# mctl5.net
KiCad netlist of a schematic drawn in EAGLE
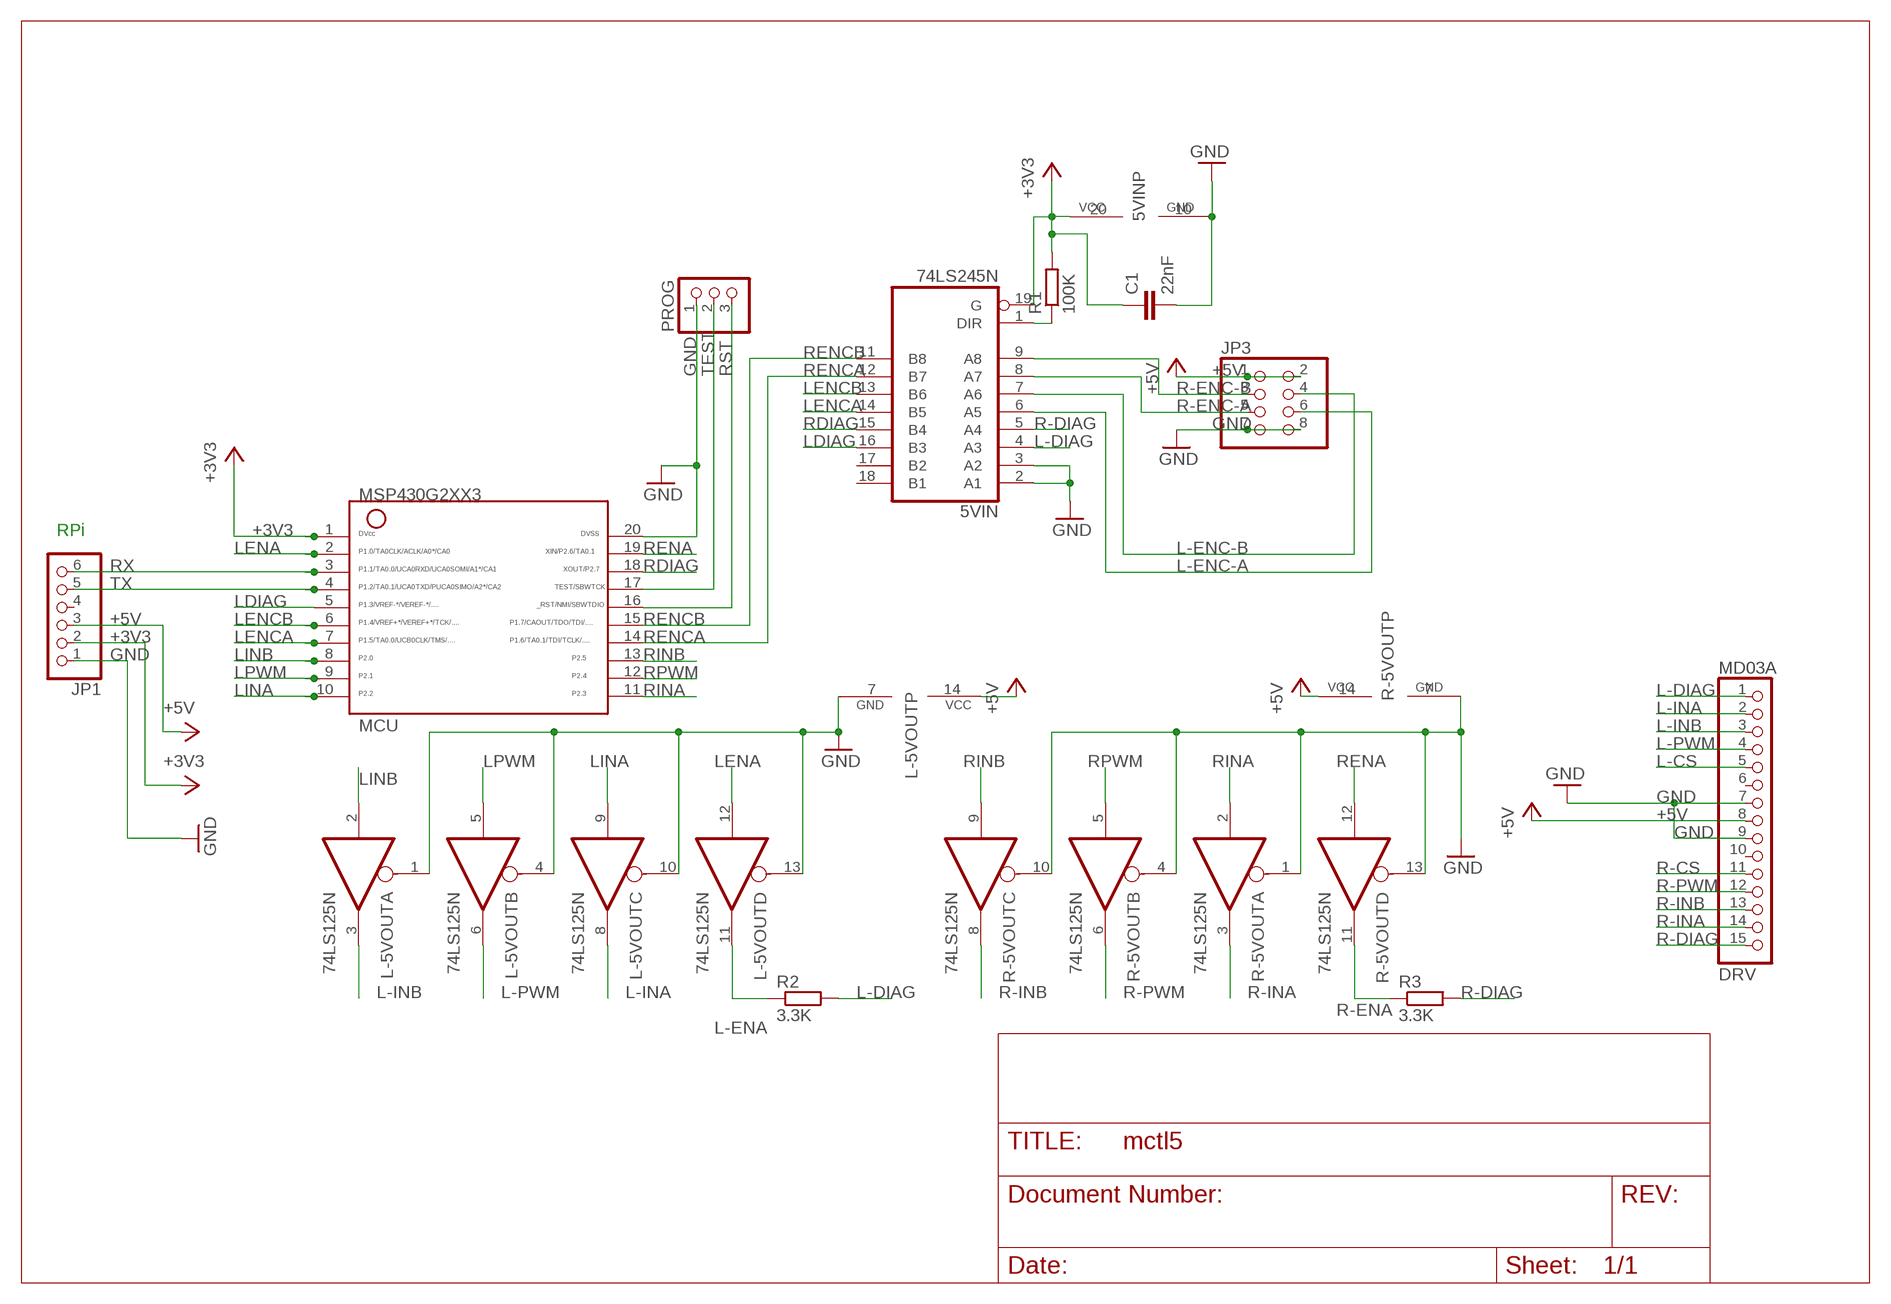
[diagram p0: schematic, sheet 1]

(export (version "E")
  (design (tool "Eeschema 10.0.6"))
  (components
    (comp (ref "5VIN")
      (value "74LS245N")
      (footprint "eagle-import:DIL20")
      (libsource (lib "eagle-import") (part "74245NLS"))
    )
    (comp (ref "C1")
      (value "22nF")
      (footprint "eagle-import:C025-024X044")
      (libsource (lib "eagle-import") (part "C-EU025-024X044"))
    )
    (comp (ref "JP1")
      (value "PINHD-1X6")
      (footprint "eagle-import:1X06")
      (libsource (lib "eagle-import") (part "PINHD-1X6"))
    )
    (comp (ref "JP3")
      (value "PINHD-2X4")
      (footprint "eagle-import:2X04")
      (libsource (lib "eagle-import") (part "PINHD-2X4"))
    )
    (comp (ref "L-5VOUT")
      (value "74LS125N")
      (footprint "eagle-import:DIL14")
      (libsource (lib "eagle-import") (part "74125NLS"))
    )
    (comp (ref "MCU")
      (value "G2XX3---N20")
      (footprint "eagle-import:N20")
      (libsource (lib "eagle-import") (part "G2XX3---N20"))
    )
    (comp (ref "MD03A")
      (value "DRV")
      (footprint "eagle-import:1X15-CB")
      (libsource (lib "eagle-import") (part "PINHD-1X15-CB"))
    )
    (comp (ref "PROG")
      (value "PINHD-1X3")
      (footprint "eagle-import:1X03")
      (libsource (lib "eagle-import") (part "PINHD-1X3"))
    )
    (comp (ref "R-5VOUT")
      (value "74LS125N")
      (footprint "eagle-import:DIL14")
      (libsource (lib "eagle-import") (part "74125NLS"))
    )
    (comp (ref "R1")
      (value "100K")
      (footprint "eagle-import:0204_7")
      (libsource (lib "eagle-import") (part "R-EU_0204/7"))
    )
    (comp (ref "R2")
      (value "3.3K")
      (footprint "eagle-import:0204_7")
      (libsource (lib "eagle-import") (part "R-EU_0204/7"))
    )
    (comp (ref "R3")
      (value "3.3K")
      (footprint "eagle-import:0204_7")
      (libsource (lib "eagle-import") (part "R-EU_0204/7"))
    )
  )
  (nets
    (net (code "1") (name "+3V3") (class "Default")
      (node (ref "5VIN") (pin "19") (pinfunction "G_19") (pintype "input"))
      (node (ref "5VIN") (pin "20") (pinfunction "VCC_20") (pintype "power_in"))
      (node (ref "C1") (pin "1") (pinfunction "1_1") (pintype "passive"))
      (node (ref "JP1") (pin "2") (pinfunction "2_2") (pintype "passive"))
      (node (ref "MCU") (pin "1") (pinfunction "1_1") (pintype "bidirectional"))
      (node (ref "R1") (pin "2") (pinfunction "2_2") (pintype "passive"))
    )
    (net (code "2") (name "+5V") (class "Default")
      (node (ref "JP1") (pin "3") (pinfunction "3_3") (pintype "passive"))
      (node (ref "JP3") (pin "1") (pinfunction "1_1") (pintype "passive"))
      (node (ref "JP3") (pin "2") (pinfunction "2_2") (pintype "passive"))
      (node (ref "L-5VOUT") (pin "14") (pinfunction "VCC_14") (pintype "power_in"))
      (node (ref "MD03A") (pin "8") (pinfunction "8_8") (pintype "passive"))
      (node (ref "R-5VOUT") (pin "14") (pinfunction "VCC_14") (pintype "power_in"))
    )
    (net (code "3") (name "/L-CS") (class "Default")
      (node (ref "MD03A") (pin "5") (pinfunction "5_5") (pintype "passive"))
    )
    (net (code "4") (name "/L-DIAG") (class "Default")
      (node (ref "5VIN") (pin "4") (pinfunction "A3_4") (pintype "bidirectional"))
      (node (ref "MD03A") (pin "1") (pinfunction "1_1") (pintype "passive"))
      (node (ref "R2") (pin "2") (pinfunction "2_2") (pintype "passive"))
    )
    (net (code "5") (name "/L-ENA") (class "Default")
      (node (ref "L-5VOUT") (pin "11") (pinfunction "O_11") (pintype "tri_state"))
      (node (ref "R2") (pin "1") (pinfunction "1_1") (pintype "passive"))
    )
    (net (code "6") (name "/L-ENC-A") (class "Default")
      (node (ref "5VIN") (pin "6") (pinfunction "A5_6") (pintype "bidirectional"))
      (node (ref "JP3") (pin "6") (pinfunction "6_6") (pintype "passive"))
    )
    (net (code "7") (name "/L-ENC-B") (class "Default")
      (node (ref "5VIN") (pin "7") (pinfunction "A6_7") (pintype "bidirectional"))
      (node (ref "JP3") (pin "4") (pinfunction "4_4") (pintype "passive"))
    )
    (net (code "8") (name "/L-INA") (class "Default")
      (node (ref "L-5VOUT") (pin "8") (pinfunction "O_8") (pintype "tri_state"))
      (node (ref "MD03A") (pin "2") (pinfunction "2_2") (pintype "passive"))
    )
    (net (code "9") (name "/L-INB") (class "Default")
      (node (ref "L-5VOUT") (pin "3") (pinfunction "O_3") (pintype "tri_state"))
      (node (ref "MD03A") (pin "3") (pinfunction "3_3") (pintype "passive"))
    )
    (net (code "10") (name "/L-PWM") (class "Default")
      (node (ref "L-5VOUT") (pin "6") (pinfunction "O_6") (pintype "tri_state"))
      (node (ref "MD03A") (pin "4") (pinfunction "4_4") (pintype "passive"))
    )
    (net (code "11") (name "/LDIAG") (class "Default")
      (node (ref "5VIN") (pin "16") (pinfunction "B3_16") (pintype "bidirectional"))
      (node (ref "MCU") (pin "5") (pinfunction "5_5") (pintype "bidirectional"))
    )
    (net (code "12") (name "/LENA") (class "Default")
      (node (ref "L-5VOUT") (pin "12") (pinfunction "I_12") (pintype "input"))
      (node (ref "MCU") (pin "2") (pinfunction "2_2") (pintype "bidirectional"))
    )
    (net (code "13") (name "/LENCA") (class "Default")
      (node (ref "5VIN") (pin "14") (pinfunction "B5_14") (pintype "bidirectional"))
      (node (ref "MCU") (pin "7") (pinfunction "7_7") (pintype "bidirectional"))
    )
    (net (code "14") (name "/LENCB") (class "Default")
      (node (ref "5VIN") (pin "13") (pinfunction "B6_13") (pintype "bidirectional"))
      (node (ref "MCU") (pin "6") (pinfunction "6_6") (pintype "bidirectional"))
    )
    (net (code "15") (name "/LINA") (class "Default")
      (node (ref "L-5VOUT") (pin "9") (pinfunction "I_9") (pintype "input"))
      (node (ref "MCU") (pin "10") (pinfunction "10_10") (pintype "bidirectional"))
    )
    (net (code "16") (name "/LINB") (class "Default")
      (node (ref "L-5VOUT") (pin "2") (pinfunction "I_2") (pintype "input"))
      (node (ref "MCU") (pin "8") (pinfunction "8_8") (pintype "bidirectional"))
    )
    (net (code "17") (name "/LPWM") (class "Default")
      (node (ref "L-5VOUT") (pin "5") (pinfunction "I_5") (pintype "input"))
      (node (ref "MCU") (pin "9") (pinfunction "9_9") (pintype "bidirectional"))
    )
    (net (code "18") (name "/R-CS") (class "Default")
      (node (ref "MD03A") (pin "11") (pinfunction "11_11") (pintype "passive"))
    )
    (net (code "19") (name "/R-DIAG") (class "Default")
      (node (ref "5VIN") (pin "5") (pinfunction "A4_5") (pintype "bidirectional"))
      (node (ref "MD03A") (pin "15") (pinfunction "15_15") (pintype "passive"))
      (node (ref "R3") (pin "2") (pinfunction "2_2") (pintype "passive"))
    )
    (net (code "20") (name "/R-ENA") (class "Default")
      (node (ref "R-5VOUT") (pin "11") (pinfunction "O_11") (pintype "tri_state"))
      (node (ref "R3") (pin "1") (pinfunction "1_1") (pintype "passive"))
    )
    (net (code "21") (name "/R-ENC-A") (class "Default")
      (node (ref "5VIN") (pin "8") (pinfunction "A7_8") (pintype "bidirectional"))
      (node (ref "JP3") (pin "5") (pinfunction "5_5") (pintype "passive"))
    )
    (net (code "22") (name "/R-ENC-B") (class "Default")
      (node (ref "5VIN") (pin "9") (pinfunction "A8_9") (pintype "bidirectional"))
      (node (ref "JP3") (pin "3") (pinfunction "3_3") (pintype "passive"))
    )
    (net (code "23") (name "/R-INA") (class "Default")
      (node (ref "MD03A") (pin "14") (pinfunction "14_14") (pintype "passive"))
      (node (ref "R-5VOUT") (pin "3") (pinfunction "O_3") (pintype "tri_state"))
    )
    (net (code "24") (name "/R-INB") (class "Default")
      (node (ref "MD03A") (pin "13") (pinfunction "13_13") (pintype "passive"))
      (node (ref "R-5VOUT") (pin "8") (pinfunction "O_8") (pintype "tri_state"))
    )
    (net (code "25") (name "/R-PWM") (class "Default")
      (node (ref "MD03A") (pin "12") (pinfunction "12_12") (pintype "passive"))
      (node (ref "R-5VOUT") (pin "6") (pinfunction "O_6") (pintype "tri_state"))
    )
    (net (code "26") (name "/RDIAG") (class "Default")
      (node (ref "5VIN") (pin "15") (pinfunction "B4_15") (pintype "bidirectional"))
      (node (ref "MCU") (pin "18") (pinfunction "18_18") (pintype "bidirectional"))
    )
    (net (code "27") (name "/RENA") (class "Default")
      (node (ref "MCU") (pin "19") (pinfunction "19_19") (pintype "bidirectional"))
      (node (ref "R-5VOUT") (pin "12") (pinfunction "I_12") (pintype "input"))
    )
    (net (code "28") (name "/RENCA") (class "Default")
      (node (ref "5VIN") (pin "12") (pinfunction "B7_12") (pintype "bidirectional"))
      (node (ref "MCU") (pin "14") (pinfunction "14_14") (pintype "bidirectional"))
    )
    (net (code "29") (name "/RENCB") (class "Default")
      (node (ref "5VIN") (pin "11") (pinfunction "B8_11") (pintype "bidirectional"))
      (node (ref "MCU") (pin "15") (pinfunction "15_15") (pintype "bidirectional"))
    )
    (net (code "30") (name "/RINA") (class "Default")
      (node (ref "MCU") (pin "11") (pinfunction "11_11") (pintype "bidirectional"))
      (node (ref "R-5VOUT") (pin "2") (pinfunction "I_2") (pintype "input"))
    )
    (net (code "31") (name "/RINB") (class "Default")
      (node (ref "MCU") (pin "13") (pinfunction "13_13") (pintype "bidirectional"))
      (node (ref "R-5VOUT") (pin "9") (pinfunction "I_9") (pintype "input"))
    )
    (net (code "32") (name "/RPWM") (class "Default")
      (node (ref "MCU") (pin "12") (pinfunction "12_12") (pintype "bidirectional"))
      (node (ref "R-5VOUT") (pin "5") (pinfunction "I_5") (pintype "input"))
    )
    (net (code "33") (name "/RST") (class "Default")
      (node (ref "MCU") (pin "16") (pinfunction "16_16") (pintype "bidirectional"))
      (node (ref "PROG") (pin "3") (pinfunction "3_3") (pintype "passive"))
    )
    (net (code "34") (name "/RX") (class "Default")
      (node (ref "JP1") (pin "6") (pinfunction "6_6") (pintype "passive"))
      (node (ref "MCU") (pin "3") (pinfunction "3_3") (pintype "bidirectional"))
    )
    (net (code "35") (name "/TEST") (class "Default")
      (node (ref "MCU") (pin "17") (pinfunction "17_17") (pintype "bidirectional"))
      (node (ref "PROG") (pin "2") (pinfunction "2_2") (pintype "passive"))
    )
    (net (code "36") (name "/TX") (class "Default")
      (node (ref "JP1") (pin "5") (pinfunction "5_5") (pintype "passive"))
      (node (ref "MCU") (pin "4") (pinfunction "4_4") (pintype "bidirectional"))
    )
    (net (code "37") (name "GND") (class "Default")
      (node (ref "5VIN") (pin "10") (pinfunction "GND_10") (pintype "power_in"))
      (node (ref "5VIN") (pin "2") (pinfunction "A1_2") (pintype "bidirectional"))
      (node (ref "5VIN") (pin "3") (pinfunction "A2_3") (pintype "bidirectional"))
      (node (ref "C1") (pin "2") (pinfunction "2_2") (pintype "passive"))
      (node (ref "JP1") (pin "1") (pinfunction "1_1") (pintype "passive"))
      (node (ref "JP3") (pin "7") (pinfunction "7_7") (pintype "passive"))
      (node (ref "JP3") (pin "8") (pinfunction "8_8") (pintype "passive"))
      (node (ref "L-5VOUT") (pin "1") (pinfunction "OE_1") (pintype "input"))
      (node (ref "L-5VOUT") (pin "10") (pinfunction "OE_10") (pintype "input"))
      (node (ref "L-5VOUT") (pin "13") (pinfunction "OE_13") (pintype "input"))
      (node (ref "L-5VOUT") (pin "4") (pinfunction "OE_4") (pintype "input"))
      (node (ref "L-5VOUT") (pin "7") (pinfunction "GND_7") (pintype "power_in"))
      (node (ref "MCU") (pin "20") (pinfunction "20_20") (pintype "bidirectional"))
      (node (ref "MD03A") (pin "7") (pinfunction "7_7") (pintype "passive"))
      (node (ref "MD03A") (pin "9") (pinfunction "9_9") (pintype "passive"))
      (node (ref "PROG") (pin "1") (pinfunction "1_1") (pintype "passive"))
      (node (ref "R-5VOUT") (pin "1") (pinfunction "OE_1") (pintype "input"))
      (node (ref "R-5VOUT") (pin "10") (pinfunction "OE_10") (pintype "input"))
      (node (ref "R-5VOUT") (pin "13") (pinfunction "OE_13") (pintype "input"))
      (node (ref "R-5VOUT") (pin "4") (pinfunction "OE_4") (pintype "input"))
      (node (ref "R-5VOUT") (pin "7") (pinfunction "GND_7") (pintype "power_in"))
    )
    (net (code "38") (name "Net-(5VINA-DIR)") (class "Default")
      (node (ref "5VIN") (pin "1") (pinfunction "DIR_1") (pintype "input"))
      (node (ref "R1") (pin "1") (pinfunction "1_1") (pintype "passive"))
    )
    (net (code "39") (name "unconnected-(5VINA-B1-Pad18)") (class "Default")
      (node (ref "5VIN") (pin "18") (pinfunction "B1_18") (pintype "bidirectional"))
    )
    (net (code "40") (name "unconnected-(5VINA-B2-Pad17)") (class "Default")
      (node (ref "5VIN") (pin "17") (pinfunction "B2_17") (pintype "bidirectional"))
    )
    (net (code "41") (name "unconnected-(JP1-Pad4)") (class "Default")
      (node (ref "JP1") (pin "4") (pinfunction "4_4") (pintype "passive"))
    )
    (net (code "42") (name "unconnected-(MD03A-Pad6)") (class "Default")
      (node (ref "MD03A") (pin "6") (pinfunction "6_6") (pintype "passive"))
    )
    (net (code "43") (name "unconnected-(MD03A-Pad10)") (class "Default")
      (node (ref "MD03A") (pin "10") (pinfunction "10_10") (pintype "passive"))
    )
  )
)
